# MB1-SD_CARD.net
KiCad netlist of a schematic drawn in Altium Designer
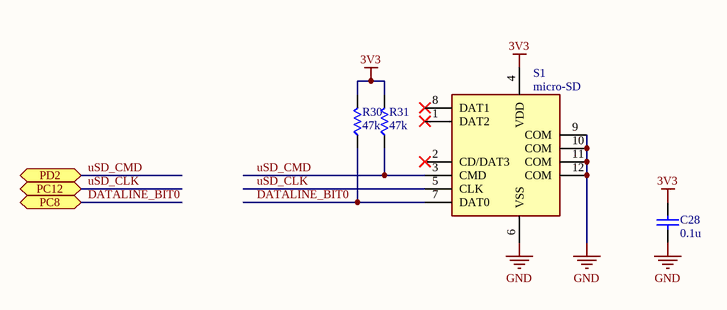
[diagram p0: MB1-SD_CARD.SchDoc]

(export (version "E")
  (design (tool "Eeschema 10.0.6"))
  (components
    (comp (ref "C28")
      (value "0.1u")
      (footprint "SM_0805_C_CERAMIC")
      (description "Non-polarity ceramic capacitor")
      (fields (field (name "Comment") "CAP_Ceramic") (field (name "PUBLISHER") "Altium Limited"))
      (libsource (lib "Copy of HLib_device_library") (part "C_Ceramic"))
    )
    (comp (ref "R30")
      (value "47k")
      (footprint "SM_0805_R")
      (description "Resistor")
      (fields (field (name "PUBLISHER") "Altium Limited"))
      (libsource (lib "Copy of HLib_device_library") (part "R"))
    )
    (comp (ref "R31")
      (value "47k")
      (footprint "SM_0805_R")
      (description "Resistor")
      (fields (field (name "PUBLISHER") "Altium Limited"))
      (libsource (lib "Copy of HLib_device_library") (part "R"))
    )
    (comp (ref "S1") (value "micro-SD") (footprint "micro-SD") (libsource (lib "MyLib") (part "micro-SD")))
  )
  (nets
    (net (code "1") (name "/DATALINE_BIT0") (class "Default")
      (node (ref "R30") (pin "1") (pinfunction "1_1") (pintype "passive"))
      (node (ref "S1") (pin "7") (pinfunction "DAT0_7") (pintype "passive"))
    )
    (net (code "2") (name "/uSD_CLK") (class "Default")
      (node (ref "S1") (pin "5") (pinfunction "CLK_5") (pintype "passive"))
    )
    (net (code "3") (name "/uSD_CMD") (class "Default")
      (node (ref "R31") (pin "1") (pinfunction "1_1") (pintype "passive"))
      (node (ref "S1") (pin "3") (pinfunction "CMD_3") (pintype "passive"))
    )
    (net (code "4") (name "3V3") (class "Default")
      (node (ref "C28") (pin "2") (pinfunction "2_2") (pintype "passive"))
      (node (ref "R30") (pin "2") (pinfunction "2_2") (pintype "passive"))
      (node (ref "R31") (pin "2") (pinfunction "2_2") (pintype "passive"))
      (node (ref "S1") (pin "4") (pinfunction "VDD_4") (pintype "passive"))
    )
    (net (code "5") (name "GND") (class "Default")
      (node (ref "C28") (pin "1") (pinfunction "1_1") (pintype "passive"))
      (node (ref "S1") (pin "10") (pinfunction "COM_10") (pintype "passive"))
      (node (ref "S1") (pin "11") (pinfunction "COM_11") (pintype "passive"))
      (node (ref "S1") (pin "12") (pinfunction "COM_12") (pintype "passive"))
      (node (ref "S1") (pin "6") (pinfunction "VSS_6") (pintype "passive"))
      (node (ref "S1") (pin "9") (pinfunction "COM_9") (pintype "passive"))
    )
    (net (code "6") (name "unconnected-(S1-CD{slash}DAT3-Pad2)") (class "Default")
      (node (ref "S1") (pin "2") (pinfunction "CD/DAT3_2") (pintype "passive+no_connect"))
    )
    (net (code "7") (name "unconnected-(S1-DAT1-Pad8)") (class "Default")
      (node (ref "S1") (pin "8") (pinfunction "DAT1_8") (pintype "passive+no_connect"))
    )
    (net (code "8") (name "unconnected-(S1-DAT2-Pad1)") (class "Default")
      (node (ref "S1") (pin "1") (pinfunction "DAT2_1") (pintype "passive+no_connect"))
    )
  )
)
